# gasbagCtrl_SingleChannel.net
KiCad netlist of a schematic drawn in Altium Designer
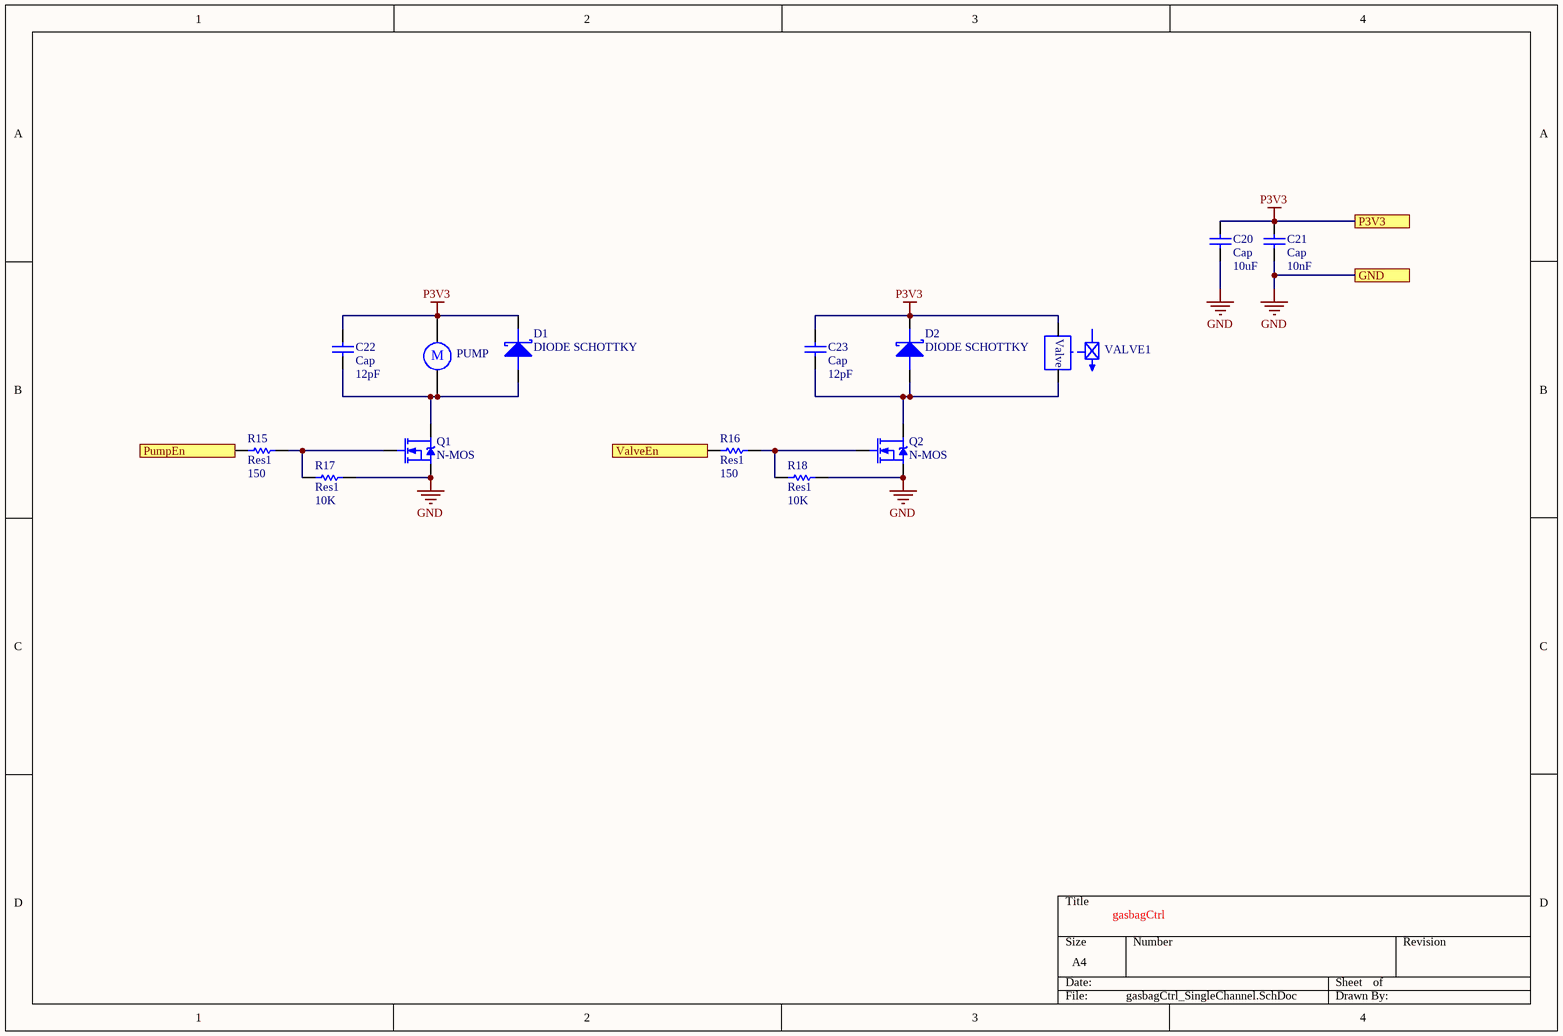
[diagram p0: gasbagCtrl_SingleChannel.SchDoc]

(export (version "E")
  (design (tool "Eeschema 10.0.6"))
  (components
    (comp (ref "B1")
      (value "PUMP")
      (footprint "BAT-2")
      (description "Motor, General Kind")
      (fields (field (name "PUBLISHER") "Altium Limited"))
      (libsource (lib "*") (part "Motor"))
    )
    (comp (ref "C20")
      (value "Cap")
      (footprint "0603C")
      (description "Capacitor")
      (fields (field (name "ALTIUM_VALUE") "10uF") (field (name "PUBLISHER") "Altium Limited"))
      (libsource (lib "Miscellaneous Devices") (part "Cap"))
    )
    (comp (ref "C21")
      (value "Cap")
      (footprint "0603C")
      (description "Capacitor")
      (fields (field (name "ALTIUM_VALUE") "10nF") (field (name "PUBLISHER") "Altium Limited"))
      (libsource (lib "Miscellaneous Devices") (part "Cap"))
    )
    (comp (ref "C22")
      (value "Cap")
      (footprint "0603C")
      (description "Capacitor")
      (fields (field (name "ALTIUM_VALUE") "12pF") (field (name "PUBLISHER") "Altium Limited"))
      (libsource (lib "Miscellaneous Devices") (part "Cap"))
    )
    (comp (ref "C23")
      (value "Cap")
      (footprint "0603C")
      (description "Capacitor")
      (fields (field (name "ALTIUM_VALUE") "12pF") (field (name "PUBLISHER") "Altium Limited"))
      (libsource (lib "Miscellaneous Devices") (part "Cap"))
    )
    (comp (ref "D1")
      (value "DIODE SCHOTTKY")
      (footprint "DO-15")
      (description "肖特基二极管")
      (libsource (lib "二极管") (part "DIODE SCHOTTKY"))
    )
    (comp (ref "D2")
      (value "DIODE SCHOTTKY")
      (footprint "DO-15")
      (description "肖特基二极管")
      (libsource (lib "二极管") (part "DIODE SCHOTTKY"))
    )
    (comp (ref "Q1")
      (value "N-MOS")
      (footprint "TO220A")
      (description "N沟道场效应管")
      (libsource (lib "MOS管") (part "N-MOS"))
    )
    (comp (ref "Q2")
      (value "N-MOS")
      (footprint "TO220A")
      (description "N沟道场效应管")
      (libsource (lib "MOS管") (part "N-MOS"))
    )
    (comp (ref "R15")
      (value "Res1")
      (footprint "0603R")
      (description "Resistor")
      (fields (field (name "ALTIUM_VALUE") "150") (field (name "PUBLISHER") "Altium Limited"))
      (libsource (lib "Miscellaneous Devices") (part "Res1"))
    )
    (comp (ref "R16")
      (value "Res1")
      (footprint "0603R")
      (description "Resistor")
      (fields (field (name "ALTIUM_VALUE") "150") (field (name "PUBLISHER") "Altium Limited"))
      (libsource (lib "Miscellaneous Devices") (part "Res1"))
    )
    (comp (ref "R17")
      (value "Res1")
      (footprint "0603R")
      (description "Resistor")
      (fields (field (name "ALTIUM_VALUE") "10K") (field (name "PUBLISHER") "Altium Limited"))
      (libsource (lib "Miscellaneous Devices") (part "Res1"))
    )
    (comp (ref "R18")
      (value "Res1")
      (footprint "0603R")
      (description "Resistor")
      (fields (field (name "ALTIUM_VALUE") "10K") (field (name "PUBLISHER") "Altium Limited"))
      (libsource (lib "Miscellaneous Devices") (part "Res1"))
    )
    (comp (ref "VALVE1") (value "Valve_1") (footprint "jack2.54") (libsource (lib "myself") (part "Valve_1")))
  )
  (nets
    (net (code "1") (name "/PumpEn") (class "Default")
      (node (ref "R15") (pin "2") (pinfunction "2_2") (pintype "passive"))
    )
    (net (code "2") (name "/ValveEn") (class "Default")
      (node (ref "R16") (pin "2") (pinfunction "2_2") (pintype "passive"))
    )
    (net (code "3") (name "GND") (class "Default")
      (node (ref "C20") (pin "1") (pinfunction "1_1") (pintype "passive"))
      (node (ref "C21") (pin "1") (pinfunction "1_1") (pintype "passive"))
      (node (ref "Q1") (pin "S") (pinfunction "S_S") (pintype "passive"))
      (node (ref "Q2") (pin "S") (pinfunction "S_S") (pintype "passive"))
      (node (ref "R17") (pin "1") (pinfunction "1_1") (pintype "passive"))
      (node (ref "R18") (pin "1") (pinfunction "1_1") (pintype "passive"))
    )
    (net (code "4") (name "Net-(B1-Pad2)") (class "Default")
      (node (ref "B1") (pin "2") (pinfunction "2_2") (pintype "passive"))
      (node (ref "C22") (pin "1") (pinfunction "1_1") (pintype "passive"))
      (node (ref "D1") (pin "A") (pinfunction "A_A") (pintype "passive"))
      (node (ref "Q1") (pin "D") (pinfunction "D_D") (pintype "passive"))
    )
    (net (code "5") (name "Net-(C23-Pad1)") (class "Default")
      (node (ref "C23") (pin "1") (pinfunction "1_1") (pintype "passive"))
      (node (ref "D2") (pin "A") (pinfunction "A_A") (pintype "passive"))
      (node (ref "Q2") (pin "D") (pinfunction "D_D") (pintype "passive"))
      (node (ref "VALVE1") (pin "1") (pinfunction "1_1") (pintype "passive"))
    )
    (net (code "6") (name "Net-(Q1-PadG)") (class "Default")
      (node (ref "Q1") (pin "G") (pinfunction "G_G") (pintype "passive"))
      (node (ref "R15") (pin "1") (pinfunction "1_1") (pintype "passive"))
      (node (ref "R17") (pin "2") (pinfunction "2_2") (pintype "passive"))
    )
    (net (code "7") (name "Net-(Q2-PadG)") (class "Default")
      (node (ref "Q2") (pin "G") (pinfunction "G_G") (pintype "passive"))
      (node (ref "R16") (pin "1") (pinfunction "1_1") (pintype "passive"))
      (node (ref "R18") (pin "2") (pinfunction "2_2") (pintype "passive"))
    )
    (net (code "8") (name "P3V3") (class "Default")
      (node (ref "B1") (pin "1") (pinfunction "1_1") (pintype "passive"))
      (node (ref "C20") (pin "2") (pinfunction "2_2") (pintype "passive"))
      (node (ref "C21") (pin "2") (pinfunction "2_2") (pintype "passive"))
      (node (ref "C22") (pin "2") (pinfunction "2_2") (pintype "passive"))
      (node (ref "C23") (pin "2") (pinfunction "2_2") (pintype "passive"))
      (node (ref "D1") (pin "K") (pinfunction "K_K") (pintype "passive"))
      (node (ref "D2") (pin "K") (pinfunction "K_K") (pintype "passive"))
      (node (ref "VALVE1") (pin "2") (pinfunction "2_2") (pintype "passive"))
    )
  )
)
